# polarization_switch_mid_redo_top_rt.net
KiCad netlist of a schematic drawn in EAGLE
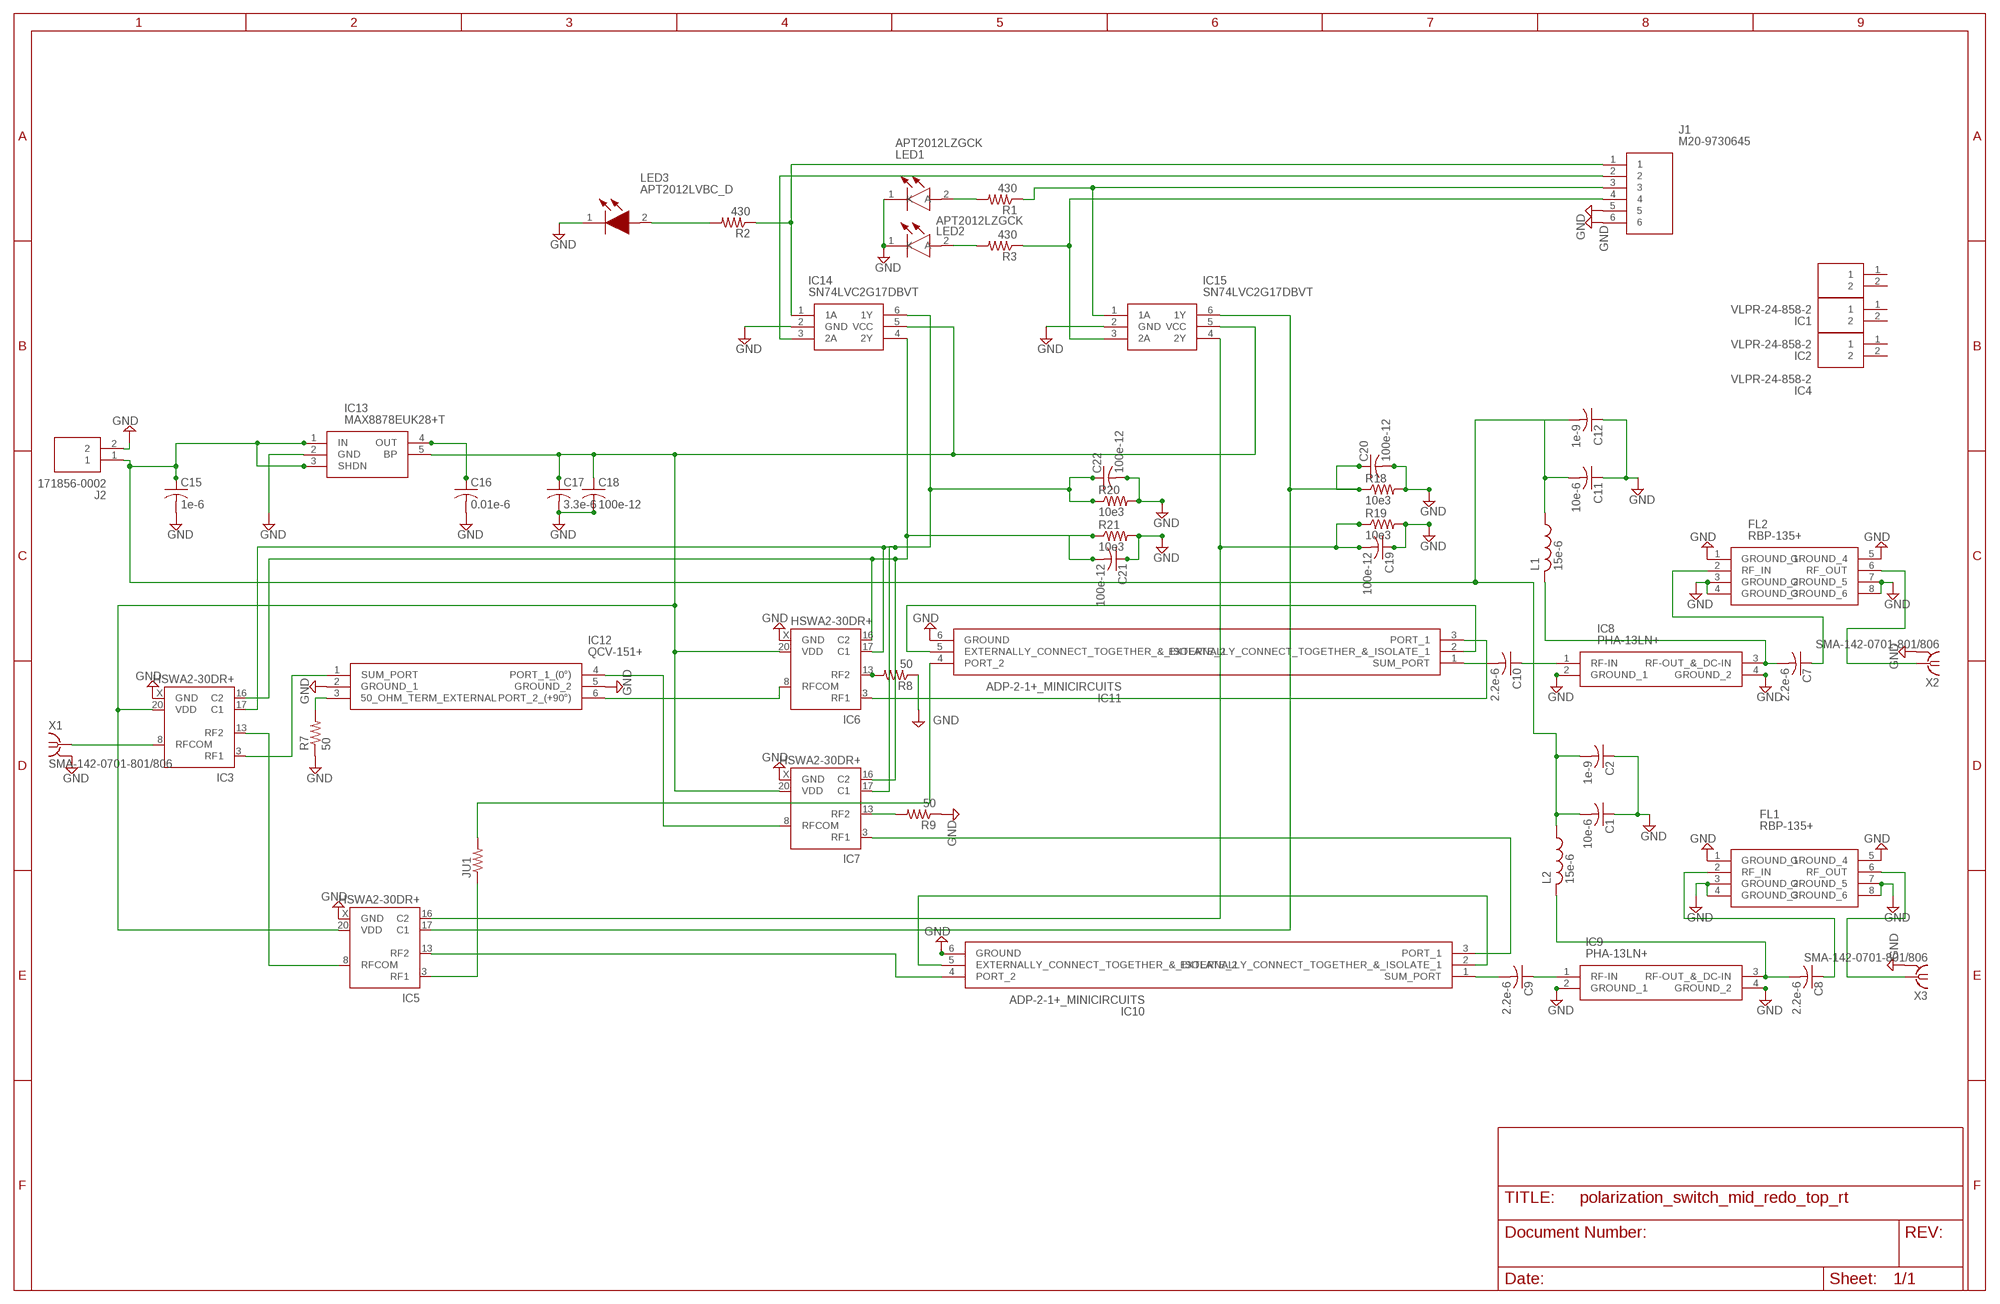
[diagram p0: schematic, sheet 1]

(export (version "E")
  (design (tool "Eeschema 10.0.6"))
  (components
    (comp (ref "C1")
      (value "10e-6")
      (footprint "eagle-import:C0603")
      (libsource (lib "eagle-import") (part "C-USC0603"))
    )
    (comp (ref "C2")
      (value "1e-9")
      (footprint "eagle-import:C0603")
      (libsource (lib "eagle-import") (part "C-USC0603"))
    )
    (comp (ref "C7")
      (value "2.2e-6")
      (footprint "eagle-import:C0603")
      (libsource (lib "eagle-import") (part "C-USC0603"))
    )
    (comp (ref "C8")
      (value "2.2e-6")
      (footprint "eagle-import:C0603")
      (libsource (lib "eagle-import") (part "C-USC0603"))
    )
    (comp (ref "C9")
      (value "2.2e-6")
      (footprint "eagle-import:C0603")
      (libsource (lib "eagle-import") (part "C-USC0603"))
    )
    (comp (ref "C10")
      (value "2.2e-6")
      (footprint "eagle-import:C0603")
      (libsource (lib "eagle-import") (part "C-USC0603"))
    )
    (comp (ref "C11")
      (value "10e-6")
      (footprint "eagle-import:C0603")
      (libsource (lib "eagle-import") (part "C-USC0603"))
    )
    (comp (ref "C12")
      (value "1e-9")
      (footprint "eagle-import:C0603")
      (libsource (lib "eagle-import") (part "C-USC0603"))
    )
    (comp (ref "C15")
      (value "1e-6")
      (footprint "eagle-import:C0603")
      (libsource (lib "eagle-import") (part "C-USC0603"))
    )
    (comp (ref "C16")
      (value "0.01e-6")
      (footprint "eagle-import:C0603")
      (libsource (lib "eagle-import") (part "C-USC0603"))
    )
    (comp (ref "C17")
      (value "3.3e-6")
      (footprint "eagle-import:C0603")
      (libsource (lib "eagle-import") (part "C-USC0603"))
    )
    (comp (ref "C18")
      (value "100e-12")
      (footprint "eagle-import:C0603")
      (libsource (lib "eagle-import") (part "C-USC0603"))
    )
    (comp (ref "C19")
      (value "100e-12")
      (footprint "eagle-import:C0603")
      (libsource (lib "eagle-import") (part "C-USC0603"))
    )
    (comp (ref "C20")
      (value "100e-12")
      (footprint "eagle-import:C0603")
      (libsource (lib "eagle-import") (part "C-USC0603"))
    )
    (comp (ref "C21")
      (value "100e-12")
      (footprint "eagle-import:C0603")
      (libsource (lib "eagle-import") (part "C-USC0603"))
    )
    (comp (ref "C22")
      (value "100e-12")
      (footprint "eagle-import:C0603")
      (libsource (lib "eagle-import") (part "C-USC0603"))
    )
    (comp (ref "FL1")
      (value "RBP-135+")
      (footprint "eagle-import:RBP135")
      (libsource (lib "eagle-import") (part "RBP-135+"))
    )
    (comp (ref "FL2")
      (value "RBP-135+")
      (footprint "eagle-import:RBP135")
      (libsource (lib "eagle-import") (part "RBP-135+"))
    )
    (comp (ref "IC1")
      (value "VLPR-24-858-2")
      (footprint "eagle-import:VLPR248582")
      (fields (field (name "RS_PART_NUMBER") "9063748"))
      (libsource (lib "eagle-import") (part "VLPR-24-858-2"))
    )
    (comp (ref "IC2")
      (value "VLPR-24-858-2")
      (footprint "eagle-import:VLPR248582")
      (fields (field (name "RS_PART_NUMBER") "9063748"))
      (libsource (lib "eagle-import") (part "VLPR-24-858-2"))
    )
    (comp (ref "IC3")
      (value "HSWA2-30DR+")
      (footprint "eagle-import:DG983-1")
      (libsource (lib "eagle-import") (part "HSWA2-30DR+"))
    )
    (comp (ref "IC4")
      (value "VLPR-24-858-2")
      (footprint "eagle-import:VLPR248582")
      (fields (field (name "RS_PART_NUMBER") "9063748"))
      (libsource (lib "eagle-import") (part "VLPR-24-858-2"))
    )
    (comp (ref "IC5")
      (value "HSWA2-30DR+")
      (footprint "eagle-import:DG983-1")
      (libsource (lib "eagle-import") (part "HSWA2-30DR+"))
    )
    (comp (ref "IC6")
      (value "HSWA2-30DR+")
      (footprint "eagle-import:DG983-1")
      (libsource (lib "eagle-import") (part "HSWA2-30DR+"))
    )
    (comp (ref "IC7")
      (value "HSWA2-30DR+")
      (footprint "eagle-import:DG983-1")
      (libsource (lib "eagle-import") (part "HSWA2-30DR+"))
    )
    (comp (ref "IC8")
      (value "PHA-13LN+")
      (footprint "eagle-import:PHA13LN")
      (libsource (lib "eagle-import") (part "PHA-13LN+"))
    )
    (comp (ref "IC9")
      (value "PHA-13LN+")
      (footprint "eagle-import:PHA13LN")
      (libsource (lib "eagle-import") (part "PHA-13LN+"))
    )
    (comp (ref "IC10")
      (value "ADP-2-1+_MINICIRCUITS")
      (footprint "eagle-import:SOTFL254P691X411-6N")
      (fields (field (name "MANUFACTURER_PART_NUMBER") "ADP-2-1+ MINICIRCUITS"))
      (libsource (lib "eagle-import") (part "ADP-2-1+_MINICIRCUITS"))
    )
    (comp (ref "IC11")
      (value "ADP-2-1+_MINICIRCUITS")
      (footprint "eagle-import:SOTFL254P691X411-6N")
      (fields (field (name "MANUFACTURER_PART_NUMBER") "ADP-2-1+ MINICIRCUITS"))
      (libsource (lib "eagle-import") (part "ADP-2-1+_MINICIRCUITS"))
    )
    (comp (ref "IC12")
      (value "QCV-151+")
      (footprint "eagle-import:QCV151")
      (libsource (lib "eagle-import") (part "QCV-151+"))
    )
    (comp (ref "IC13")
      (value "MAX8878EUK28+T")
      (footprint "eagle-import:SOT95P280X145-5N")
      (libsource (lib "eagle-import") (part "MAX8878EUK28+T"))
    )
    (comp (ref "IC14")
      (value "SN74LVC2G17DBVT")
      (footprint "eagle-import:SOT95P280X145-6N")
      (fields
        (field (name "MOUSER_PART_NUMBER") "595-SN74LVC2G17DBVT")
        (field (name "RS_PART_NUMBER") "6628944P")
      )
      (libsource (lib "eagle-import") (part "SN74LVC2G17DBVT"))
    )
    (comp (ref "IC15")
      (value "SN74LVC2G17DBVT")
      (footprint "eagle-import:SOT95P280X145-6N")
      (fields
        (field (name "MOUSER_PART_NUMBER") "595-SN74LVC2G17DBVT")
        (field (name "RS_PART_NUMBER") "6628944P")
      )
      (libsource (lib "eagle-import") (part "SN74LVC2G17DBVT"))
    )
    (comp (ref "J1")
      (value "M20-9730645")
      (footprint "eagle-import:HDRV6W66P0X254_1X6_1524X254X96")
      (fields (field (name "MOUSER_PART_NUMBER") "855-M20-9730645"))
      (libsource (lib "eagle-import") (part "M20-9730645"))
    )
    (comp (ref "J2")
      (value "171856-0002")
      (footprint "eagle-import:SHDR2W90P0X254_1X2_493X635X106")
      (fields
        (field (name "MOUSER_PART_NUMBER") "538-171856-0002")
        (field (name "RS_PART_NUMBER") "7922884P")
      )
      (libsource (lib "eagle-import") (part "171856-0002"))
    )
    (comp (ref "JU1")
      (value "R-US_R1206")
      (footprint "eagle-import:R1206")
      (libsource (lib "eagle-import") (part "rcl_jumper_pads_R-US_R1206"))
    )
    (comp (ref "L1")
      (value "15e-6")
      (footprint "eagle-import:L3225M")
      (libsource (lib "eagle-import") (part "L-USL3225M"))
    )
    (comp (ref "L2")
      (value "15e-6")
      (footprint "eagle-import:L3225M")
      (libsource (lib "eagle-import") (part "L-USL3225M"))
    )
    (comp (ref "LED1")
      (value "APT2012LZGCK")
      (footprint "eagle-import:LEDC2012X85N")
      (fields (field (name "MOUSER_PART_NUMBER") "604-APT2012LZGCK"))
      (libsource (lib "eagle-import") (part "APT2012LZGCK"))
    )
    (comp (ref "LED2")
      (value "APT2012LZGCK")
      (footprint "eagle-import:LEDC2012X85N")
      (fields (field (name "MOUSER_PART_NUMBER") "604-APT2012LZGCK"))
      (libsource (lib "eagle-import") (part "APT2012LZGCK"))
    )
    (comp (ref "LED3")
      (value "APT2012LVBC_D")
      (footprint "eagle-import:LEDC2012X85N")
      (fields
        (field (name "ARROW_PART_NUMBER") "APT2012LVBC/D")
        (field (name "MOUSER_PART_NUMBER") "604-APT2012LVBCD")
      )
      (libsource (lib "eagle-import") (part "APT2012LVBC_D"))
    )
    (comp (ref "R1")
      (value "430")
      (footprint "eagle-import:R0603")
      (libsource (lib "eagle-import") (part "R-US_R0603"))
    )
    (comp (ref "R2")
      (value "430")
      (footprint "eagle-import:R0603")
      (libsource (lib "eagle-import") (part "R-US_R0603"))
    )
    (comp (ref "R3")
      (value "430")
      (footprint "eagle-import:R0603")
      (libsource (lib "eagle-import") (part "R-US_R0603"))
    )
    (comp (ref "R7")
      (value "50")
      (footprint "eagle-import:R0603")
      (libsource (lib "eagle-import") (part "R-US_R0603"))
    )
    (comp (ref "R8")
      (value "50")
      (footprint "eagle-import:R0603")
      (libsource (lib "eagle-import") (part "R-US_R0603"))
    )
    (comp (ref "R9")
      (value "50")
      (footprint "eagle-import:R0603")
      (libsource (lib "eagle-import") (part "R-US_R0603"))
    )
    (comp (ref "R18")
      (value "10e3")
      (footprint "eagle-import:R0603")
      (libsource (lib "eagle-import") (part "R-US_R0603"))
    )
    (comp (ref "R19")
      (value "10e3")
      (footprint "eagle-import:R0603")
      (libsource (lib "eagle-import") (part "R-US_R0603"))
    )
    (comp (ref "R20")
      (value "10e3")
      (footprint "eagle-import:R0603")
      (libsource (lib "eagle-import") (part "R-US_R0603"))
    )
    (comp (ref "R21")
      (value "10e3")
      (footprint "eagle-import:R0603")
      (libsource (lib "eagle-import") (part "R-US_R0603"))
    )
    (comp (ref "X1")
      (value "SMA-142-0701-801/806")
      (footprint "eagle-import:J502-ND-142-0701-801_806")
      (fields (field (name "MF") "JOHNSON COMPONENTS") (field (name "MPN") "142-0701-801"))
      (libsource (lib "eagle-import") (part "SMA-142-0701-801/806"))
    )
    (comp (ref "X2")
      (value "SMA-142-0701-801/806")
      (footprint "eagle-import:J502-ND-142-0701-801_806")
      (fields (field (name "MF") "JOHNSON COMPONENTS") (field (name "MPN") "142-0701-801"))
      (libsource (lib "eagle-import") (part "SMA-142-0701-801/806"))
    )
    (comp (ref "X3")
      (value "SMA-142-0701-801/806")
      (footprint "eagle-import:J502-ND-142-0701-801_806")
      (fields (field (name "MF") "JOHNSON COMPONENTS") (field (name "MPN") "142-0701-801"))
      (libsource (lib "eagle-import") (part "SMA-142-0701-801/806"))
    )
  )
  (nets
    (net (code "1") (name "GND") (class "Default")
      (node (ref "C1") (pin "1") (pinfunction "1_1") (pintype "passive"))
      (node (ref "C11") (pin "1") (pinfunction "1_1") (pintype "passive"))
      (node (ref "C12") (pin "1") (pinfunction "1_1") (pintype "passive"))
      (node (ref "C15") (pin "2") (pinfunction "2_2") (pintype "passive"))
      (node (ref "C16") (pin "2") (pinfunction "2_2") (pintype "passive"))
      (node (ref "C17") (pin "2") (pinfunction "2_2") (pintype "passive"))
      (node (ref "C18") (pin "2") (pinfunction "2_2") (pintype "passive"))
      (node (ref "C19") (pin "1") (pinfunction "1_1") (pintype "passive"))
      (node (ref "C2") (pin "1") (pinfunction "1_1") (pintype "passive"))
      (node (ref "C20") (pin "2") (pinfunction "2_2") (pintype "passive"))
      (node (ref "C21") (pin "1") (pinfunction "1_1") (pintype "passive"))
      (node (ref "C22") (pin "2") (pinfunction "2_2") (pintype "passive"))
      (node (ref "FL1") (pin "1") (pinfunction "GROUND_1_1") (pintype "bidirectional"))
      (node (ref "FL1") (pin "3") (pinfunction "GROUND_2_3") (pintype "bidirectional"))
      (node (ref "FL1") (pin "4") (pinfunction "GROUND_3_4") (pintype "bidirectional"))
      (node (ref "FL1") (pin "5") (pinfunction "GROUND_4_5") (pintype "bidirectional"))
      (node (ref "FL1") (pin "7") (pinfunction "GROUND_5_7") (pintype "bidirectional"))
      (node (ref "FL1") (pin "8") (pinfunction "GROUND_6_8") (pintype "bidirectional"))
      (node (ref "FL2") (pin "1") (pinfunction "GROUND_1_1") (pintype "bidirectional"))
      (node (ref "FL2") (pin "3") (pinfunction "GROUND_2_3") (pintype "bidirectional"))
      (node (ref "FL2") (pin "4") (pinfunction "GROUND_3_4") (pintype "bidirectional"))
      (node (ref "FL2") (pin "5") (pinfunction "GROUND_4_5") (pintype "bidirectional"))
      (node (ref "FL2") (pin "7") (pinfunction "GROUND_5_7") (pintype "bidirectional"))
      (node (ref "FL2") (pin "8") (pinfunction "GROUND_6_8") (pintype "bidirectional"))
      (node (ref "IC10") (pin "6") (pinfunction "GROUND_6") (pintype "bidirectional"))
      (node (ref "IC11") (pin "6") (pinfunction "GROUND_6") (pintype "bidirectional"))
      (node (ref "IC12") (pin "2") (pinfunction "GROUND_1_2") (pintype "bidirectional"))
      (node (ref "IC12") (pin "5") (pinfunction "GROUND_2_5") (pintype "bidirectional"))
      (node (ref "IC13") (pin "2") (pinfunction "GND_2") (pintype "power_in"))
      (node (ref "IC14") (pin "2") (pinfunction "GND_2") (pintype "bidirectional"))
      (node (ref "IC15") (pin "2") (pinfunction "GND_2") (pintype "bidirectional"))
      (node (ref "IC3") (pin "X") (pinfunction "GND_X") (pintype "power_in"))
      (node (ref "IC5") (pin "X") (pinfunction "GND_X") (pintype "power_in"))
      (node (ref "IC6") (pin "X") (pinfunction "GND_X") (pintype "power_in"))
      (node (ref "IC7") (pin "X") (pinfunction "GND_X") (pintype "power_in"))
      (node (ref "IC8") (pin "2") (pinfunction "GROUND_1_2") (pintype "bidirectional"))
      (node (ref "IC8") (pin "4") (pinfunction "GROUND_2_4") (pintype "bidirectional"))
      (node (ref "IC9") (pin "2") (pinfunction "GROUND_1_2") (pintype "bidirectional"))
      (node (ref "IC9") (pin "4") (pinfunction "GROUND_2_4") (pintype "bidirectional"))
      (node (ref "J1") (pin "5") (pinfunction "5_5") (pintype "bidirectional"))
      (node (ref "J1") (pin "6") (pinfunction "6_6") (pintype "bidirectional"))
      (node (ref "J2") (pin "2") (pinfunction "2_2") (pintype "bidirectional"))
      (node (ref "LED1") (pin "1") (pinfunction "K_1") (pintype "bidirectional"))
      (node (ref "LED2") (pin "1") (pinfunction "K_1") (pintype "bidirectional"))
      (node (ref "LED3") (pin "1") (pinfunction "K_1") (pintype "bidirectional"))
      (node (ref "R18") (pin "2") (pinfunction "2_2") (pintype "passive"))
      (node (ref "R19") (pin "2") (pinfunction "2_2") (pintype "passive"))
      (node (ref "R20") (pin "2") (pinfunction "2_2") (pintype "passive"))
      (node (ref "R21") (pin "2") (pinfunction "2_2") (pintype "passive"))
      (node (ref "R7") (pin "1") (pinfunction "1_1") (pintype "passive"))
      (node (ref "R8") (pin "1") (pinfunction "1_1") (pintype "passive"))
      (node (ref "R9") (pin "1") (pinfunction "1_1") (pintype "passive"))
      (node (ref "X1") (pin "G@1") (pinfunction "2_G@1") (pintype "passive"))
      (node (ref "X1") (pin "G@2") (pinfunction "2_G@2") (pintype "passive"))
      (node (ref "X1") (pin "G@3") (pinfunction "2_G@3") (pintype "passive"))
      (node (ref "X1") (pin "G@4") (pinfunction "2_G@4") (pintype "passive"))
      (node (ref "X2") (pin "G@1") (pinfunction "2_G@1") (pintype "passive"))
      (node (ref "X2") (pin "G@2") (pinfunction "2_G@2") (pintype "passive"))
      (node (ref "X2") (pin "G@3") (pinfunction "2_G@3") (pintype "passive"))
      (node (ref "X2") (pin "G@4") (pinfunction "2_G@4") (pintype "passive"))
      (node (ref "X3") (pin "G@1") (pinfunction "2_G@1") (pintype "passive"))
      (node (ref "X3") (pin "G@2") (pinfunction "2_G@2") (pintype "passive"))
      (node (ref "X3") (pin "G@3") (pinfunction "2_G@3") (pintype "passive"))
      (node (ref "X3") (pin "G@4") (pinfunction "2_G@4") (pintype "passive"))
    )
    (net (code "2") (name "Net-(FL1-RF_IN)") (class "Default")
      (node (ref "C8") (pin "1") (pinfunction "1_1") (pintype "passive"))
      (node (ref "FL1") (pin "2") (pinfunction "RF_IN_2") (pintype "bidirectional"))
    )
    (net (code "3") (name "Net-(FL1-RF_OUT)") (class "Default")
      (node (ref "FL1") (pin "6") (pinfunction "RF_OUT_6") (pintype "bidirectional"))
      (node (ref "X3") (pin "1") (pinfunction "1_1") (pintype "passive"))
    )
    (net (code "4") (name "Net-(FL2-RF_IN)") (class "Default")
      (node (ref "C7") (pin "1") (pinfunction "1_1") (pintype "passive"))
      (node (ref "FL2") (pin "2") (pinfunction "RF_IN_2") (pintype "bidirectional"))
    )
    (net (code "5") (name "Net-(FL2-RF_OUT)") (class "Default")
      (node (ref "FL2") (pin "6") (pinfunction "RF_OUT_6") (pintype "bidirectional"))
      (node (ref "X2") (pin "1") (pinfunction "1_1") (pintype "passive"))
    )
    (net (code "6") (name "Net-(IC3A-RF2)") (class "Default")
      (node (ref "IC3") (pin "13") (pinfunction "RF2_13") (pintype "passive"))
      (node (ref "IC5") (pin "8") (pinfunction "RFCOM_8") (pintype "passive"))
    )
    (net (code "7") (name "Net-(IC3A-RFCOM)") (class "Default")
      (node (ref "IC3") (pin "8") (pinfunction "RFCOM_8") (pintype "passive"))
      (node (ref "X1") (pin "1") (pinfunction "1_1") (pintype "passive"))
    )
    (net (code "8") (name "Net-(IC5A-RF1)") (class "Default")
      (node (ref "IC5") (pin "3") (pinfunction "RF1_3") (pintype "passive"))
      (node (ref "JU1") (pin "1") (pinfunction "1_1") (pintype "passive"))
    )
    (net (code "9") (name "Net-(IC6A-RF2)") (class "Default")
      (node (ref "IC6") (pin "13") (pinfunction "RF2_13") (pintype "passive"))
      (node (ref "R8") (pin "2") (pinfunction "2_2") (pintype "passive"))
    )
    (net (code "10") (name "Net-(IC7A-RF2)") (class "Default")
      (node (ref "IC7") (pin "13") (pinfunction "RF2_13") (pintype "passive"))
      (node (ref "R9") (pin "2") (pinfunction "2_2") (pintype "passive"))
    )
    (net (code "11") (name "Net-(IC8-RF-IN)") (class "Default")
      (node (ref "C10") (pin "1") (pinfunction "1_1") (pintype "passive"))
      (node (ref "IC8") (pin "1") (pinfunction "RF-IN_1") (pintype "bidirectional"))
    )
    (net (code "12") (name "Net-(IC8-RF-OUT_&_DC-IN)") (class "Default")
      (node (ref "C7") (pin "2") (pinfunction "2_2") (pintype "passive"))
      (node (ref "IC8") (pin "3") (pinfunction "RF-OUT_&_DC-IN_3") (pintype "bidirectional"))
      (node (ref "L1") (pin "2") (pinfunction "2_2") (pintype "passive"))
    )
    (net (code "13") (name "Net-(IC9-RF-IN)") (class "Default")
      (node (ref "C9") (pin "1") (pinfunction "1_1") (pintype "passive"))
      (node (ref "IC9") (pin "1") (pinfunction "RF-IN_1") (pintype "bidirectional"))
    )
    (net (code "14") (name "Net-(IC9-RF-OUT_&_DC-IN)") (class "Default")
      (node (ref "C8") (pin "2") (pinfunction "2_2") (pintype "passive"))
      (node (ref "IC9") (pin "3") (pinfunction "RF-OUT_&_DC-IN_3") (pintype "bidirectional"))
      (node (ref "L2") (pin "2") (pinfunction "2_2") (pintype "passive"))
    )
    (net (code "15") (name "Net-(IC10-EXTERNALLY_CONNECT_TOGETHER_&_ISOLATE_1)") (class "Default")
      (node (ref "IC10") (pin "2") (pinfunction "EXTERNALLY_CONNECT_TOGETHER_&_ISOLATE_1_2") (pintype "bidirectional"))
      (node (ref "IC10") (pin "5") (pinfunction "EXTERNALLY_CONNECT_TOGETHER_&_ISOLATE_2_5") (pintype "bidirectional"))
    )
    (net (code "16") (name "Net-(IC10-PORT_1)") (class "Default")
      (node (ref "IC10") (pin "3") (pinfunction "PORT_1_3") (pintype "bidirectional"))
      (node (ref "IC7") (pin "3") (pinfunction "RF1_3") (pintype "passive"))
    )
    (net (code "17") (name "Net-(IC10-PORT_2)") (class "Default")
      (node (ref "IC10") (pin "4") (pinfunction "PORT_2_4") (pintype "bidirectional"))
      (node (ref "IC5") (pin "13") (pinfunction "RF2_13") (pintype "passive"))
    )
    (net (code "18") (name "Net-(IC10-SUM_PORT)") (class "Default")
      (node (ref "C9") (pin "2") (pinfunction "2_2") (pintype "passive"))
      (node (ref "IC10") (pin "1") (pinfunction "SUM_PORT_1") (pintype "bidirectional"))
    )
    (net (code "19") (name "Net-(IC11-EXTERNALLY_CONNECT_TOGETHER_&_ISOLATE_1)") (class "Default")
      (node (ref "IC11") (pin "2") (pinfunction "EXTERNALLY_CONNECT_TOGETHER_&_ISOLATE_1_2") (pintype "bidirectional"))
      (node (ref "IC11") (pin "5") (pinfunction "EXTERNALLY_CONNECT_TOGETHER_&_ISOLATE_2_5") (pintype "bidirectional"))
    )
    (net (code "20") (name "Net-(IC11-PORT_1)") (class "Default")
      (node (ref "IC11") (pin "3") (pinfunction "PORT_1_3") (pintype "bidirectional"))
      (node (ref "IC6") (pin "3") (pinfunction "RF1_3") (pintype "passive"))
    )
    (net (code "21") (name "Net-(IC11-PORT_2)") (class "Default")
      (node (ref "IC11") (pin "4") (pinfunction "PORT_2_4") (pintype "bidirectional"))
      (node (ref "JU1") (pin "2") (pinfunction "2_2") (pintype "passive"))
    )
    (net (code "22") (name "Net-(IC11-SUM_PORT)") (class "Default")
      (node (ref "C10") (pin "2") (pinfunction "2_2") (pintype "passive"))
      (node (ref "IC11") (pin "1") (pinfunction "SUM_PORT_1") (pintype "bidirectional"))
    )
    (net (code "23") (name "Net-(IC12-50_OHM_TERM_EXTERNAL)") (class "Default")
      (node (ref "IC12") (pin "3") (pinfunction "50_OHM_TERM_EXTERNAL_3") (pintype "bidirectional"))
      (node (ref "R7") (pin "2") (pinfunction "2_2") (pintype "passive"))
    )
    (net (code "24") (name "Net-(IC12-PORT_1_(0°))") (class "Default")
      (node (ref "IC12") (pin "4") (pinfunction "PORT_1_(0°)_4") (pintype "bidirectional"))
      (node (ref "IC7") (pin "8") (pinfunction "RFCOM_8") (pintype "passive"))
    )
    (net (code "25") (name "Net-(IC12-PORT_2_(+90°))") (class "Default")
      (node (ref "IC12") (pin "6") (pinfunction "PORT_2_(+90°)_6") (pintype "bidirectional"))
      (node (ref "IC6") (pin "8") (pinfunction "RFCOM_8") (pintype "passive"))
    )
    (net (code "26") (name "Net-(IC12-SUM_PORT)") (class "Default")
      (node (ref "IC12") (pin "1") (pinfunction "SUM_PORT_1") (pintype "bidirectional"))
      (node (ref "IC3") (pin "3") (pinfunction "RF1_3") (pintype "passive"))
    )
    (net (code "27") (name "Net-(IC13-BP)") (class "Default")
      (node (ref "C17") (pin "1") (pinfunction "1_1") (pintype "passive"))
      (node (ref "C18") (pin "1") (pinfunction "1_1") (pintype "passive"))
      (node (ref "IC13") (pin "5") (pinfunction "BP_5") (pintype "bidirectional"))
      (node (ref "IC14") (pin "5") (pinfunction "VCC_5") (pintype "bidirectional"))
      (node (ref "IC15") (pin "5") (pinfunction "VCC_5") (pintype "bidirectional"))
      (node (ref "IC3") (pin "20") (pinfunction "VDD_20") (pintype "input"))
      (node (ref "IC5") (pin "20") (pinfunction "VDD_20") (pintype "input"))
      (node (ref "IC6") (pin "20") (pinfunction "VDD_20") (pintype "input"))
      (node (ref "IC7") (pin "20") (pinfunction "VDD_20") (pintype "input"))
    )
    (net (code "28") (name "Net-(IC13-IN)") (class "Default")
      (node (ref "C1") (pin "2") (pinfunction "2_2") (pintype "passive"))
      (node (ref "C11") (pin "2") (pinfunction "2_2") (pintype "passive"))
      (node (ref "C12") (pin "2") (pinfunction "2_2") (pintype "passive"))
      (node (ref "C15") (pin "1") (pinfunction "1_1") (pintype "passive"))
      (node (ref "C2") (pin "2") (pinfunction "2_2") (pintype "passive"))
      (node (ref "IC13") (pin "1") (pinfunction "IN_1") (pintype "input"))
      (node (ref "IC13") (pin "3") (pinfunction "SHDN_3") (pintype "bidirectional"))
      (node (ref "J2") (pin "1") (pinfunction "1_1") (pintype "bidirectional"))
      (node (ref "L1") (pin "1") (pinfunction "1_1") (pintype "passive"))
      (node (ref "L2") (pin "1") (pinfunction "1_1") (pintype "passive"))
    )
    (net (code "29") (name "Net-(IC13-OUT)") (class "Default")
      (node (ref "C16") (pin "1") (pinfunction "1_1") (pintype "passive"))
      (node (ref "IC13") (pin "4") (pinfunction "OUT_4") (pintype "output"))
    )
    (net (code "30") (name "Net-(IC14-1A)") (class "Default")
      (node (ref "IC14") (pin "1") (pinfunction "1A_1") (pintype "bidirectional"))
      (node (ref "J1") (pin "1") (pinfunction "1_1") (pintype "bidirectional"))
      (node (ref "R2") (pin "1") (pinfunction "1_1") (pintype "passive"))
    )
    (net (code "31") (name "Net-(IC14-1Y)") (class "Default")
      (node (ref "C22") (pin "1") (pinfunction "1_1") (pintype "passive"))
      (node (ref "IC14") (pin "6") (pinfunction "1Y_6") (pintype "bidirectional"))
      (node (ref "IC3") (pin "17") (pinfunction "C1_17") (pintype "passive"))
      (node (ref "IC6") (pin "17") (pinfunction "C1_17") (pintype "passive"))
      (node (ref "IC7") (pin "17") (pinfunction "C1_17") (pintype "passive"))
      (node (ref "R20") (pin "1") (pinfunction "1_1") (pintype "passive"))
    )
    (net (code "32") (name "Net-(IC14-2A)") (class "Default")
      (node (ref "IC14") (pin "3") (pinfunction "2A_3") (pintype "bidirectional"))
      (node (ref "J1") (pin "2") (pinfunction "2_2") (pintype "bidirectional"))
    )
    (net (code "33") (name "Net-(IC14-2Y)") (class "Default")
      (node (ref "C21") (pin "2") (pinfunction "2_2") (pintype "passive"))
      (node (ref "IC14") (pin "4") (pinfunction "2Y_4") (pintype "bidirectional"))
      (node (ref "IC3") (pin "16") (pinfunction "C2_16") (pintype "passive"))
      (node (ref "IC6") (pin "16") (pinfunction "C2_16") (pintype "passive"))
      (node (ref "IC7") (pin "16") (pinfunction "C2_16") (pintype "passive"))
      (node (ref "R21") (pin "1") (pinfunction "1_1") (pintype "passive"))
    )
    (net (code "34") (name "Net-(IC15-1A)") (class "Default")
      (node (ref "IC15") (pin "1") (pinfunction "1A_1") (pintype "bidirectional"))
      (node (ref "J1") (pin "3") (pinfunction "3_3") (pintype "bidirectional"))
      (node (ref "R1") (pin "1") (pinfunction "1_1") (pintype "passive"))
    )
    (net (code "35") (name "Net-(IC15-1Y)") (class "Default")
      (node (ref "C20") (pin "1") (pinfunction "1_1") (pintype "passive"))
      (node (ref "IC15") (pin "6") (pinfunction "1Y_6") (pintype "bidirectional"))
      (node (ref "IC5") (pin "17") (pinfunction "C1_17") (pintype "passive"))
      (node (ref "R18") (pin "1") (pinfunction "1_1") (pintype "passive"))
    )
    (net (code "36") (name "Net-(IC15-2A)") (class "Default")
      (node (ref "IC15") (pin "3") (pinfunction "2A_3") (pintype "bidirectional"))
      (node (ref "J1") (pin "4") (pinfunction "4_4") (pintype "bidirectional"))
      (node (ref "R3") (pin "1") (pinfunction "1_1") (pintype "passive"))
    )
    (net (code "37") (name "Net-(IC15-2Y)") (class "Default")
      (node (ref "C19") (pin "2") (pinfunction "2_2") (pintype "passive"))
      (node (ref "IC15") (pin "4") (pinfunction "2Y_4") (pintype "bidirectional"))
      (node (ref "IC5") (pin "16") (pinfunction "C2_16") (pintype "passive"))
      (node (ref "R19") (pin "1") (pinfunction "1_1") (pintype "passive"))
    )
    (net (code "38") (name "Net-(LED1-A)") (class "Default")
      (node (ref "LED1") (pin "2") (pinfunction "A_2") (pintype "bidirectional"))
      (node (ref "R1") (pin "2") (pinfunction "2_2") (pintype "passive"))
    )
    (net (code "39") (name "Net-(LED2-A)") (class "Default")
      (node (ref "LED2") (pin "2") (pinfunction "A_2") (pintype "bidirectional"))
      (node (ref "R3") (pin "2") (pinfunction "2_2") (pintype "passive"))
    )
    (net (code "40") (name "Net-(LED3-A)") (class "Default")
      (node (ref "LED3") (pin "2") (pinfunction "A_2") (pintype "bidirectional"))
      (node (ref "R2") (pin "2") (pinfunction "2_2") (pintype "passive"))
    )
    (net (code "41") (name "unconnected-(IC1-Pad1)") (class "Default")
      (node (ref "IC1") (pin "1") (pinfunction "1_1") (pintype "bidirectional"))
    )
    (net (code "42") (name "unconnected-(IC1-Pad2)") (class "Default")
      (node (ref "IC1") (pin "2") (pinfunction "2_2") (pintype "bidirectional"))
    )
    (net (code "43") (name "unconnected-(IC2-Pad1)") (class "Default")
      (node (ref "IC2") (pin "1") (pinfunction "1_1") (pintype "bidirectional"))
    )
    (net (code "44") (name "unconnected-(IC2-Pad2)") (class "Default")
      (node (ref "IC2") (pin "2") (pinfunction "2_2") (pintype "bidirectional"))
    )
    (net (code "45") (name "unconnected-(IC4-Pad1)") (class "Default")
      (node (ref "IC4") (pin "1") (pinfunction "1_1") (pintype "bidirectional"))
    )
    (net (code "46") (name "unconnected-(IC4-Pad2)") (class "Default")
      (node (ref "IC4") (pin "2") (pinfunction "2_2") (pintype "bidirectional"))
    )
  )
)
